# Base_Station_2_5.net
KiCad netlist of a schematic drawn in EAGLE
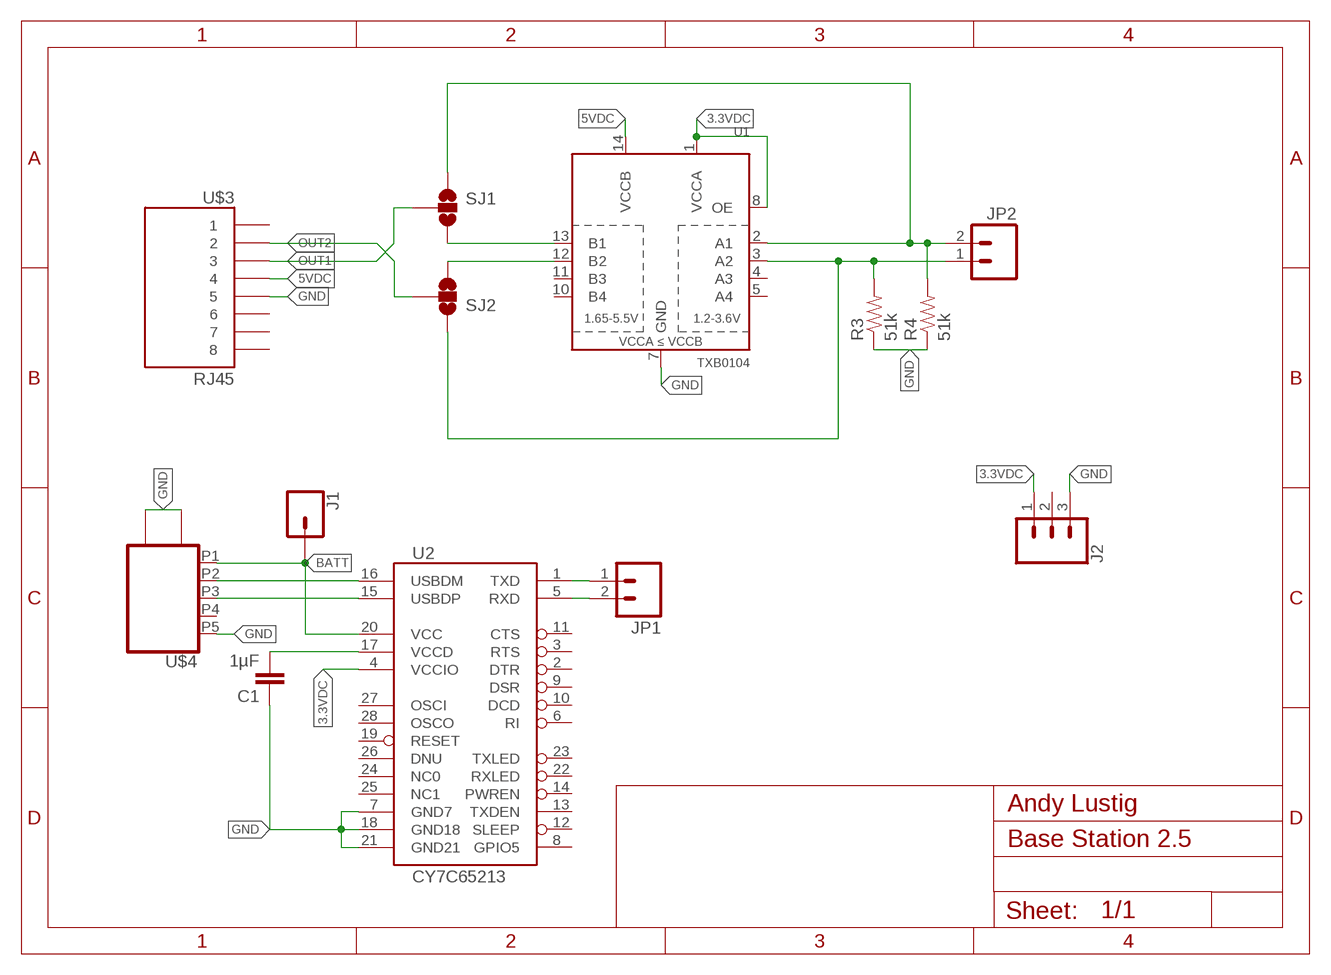
[diagram p0: schematic, sheet 1]

(export (version "E")
  (design (tool "Eeschema 10.0.6"))
  (components
    (comp (ref "C1")
      (value "1µF")
      (footprint "eagle-import:0603")
      (libsource (lib "eagle-import") (part "0.1UF-0603-25V-5%"))
    )
    (comp (ref "J1")
      (value "CONN_01PTH_NO_SILK_YES_STOP")
      (footprint "eagle-import:1X01_NO_SILK")
      (libsource (lib "eagle-import") (part "CONN_01PTH_NO_SILK_YES_STOP"))
    )
    (comp (ref "J2")
      (value "CONN_031X03_NO_SILK")
      (footprint "eagle-import:1X03_NO_SILK")
      (libsource (lib "eagle-import") (part "CONN_031X03_NO_SILK"))
    )
    (comp (ref "JP1")
      (value "M021X02_NO_SILK")
      (footprint "eagle-import:1X02_NO_SILK")
      (libsource (lib "eagle-import") (part "M021X02_NO_SILK"))
    )
    (comp (ref "JP2")
      (value "M021X02_NO_SILK")
      (footprint "eagle-import:1X02_NO_SILK")
      (libsource (lib "eagle-import") (part "M021X02_NO_SILK"))
    )
    (comp (ref "R3")
      (value "51k")
      (footprint "eagle-import:0805")
      (libsource (lib "eagle-import") (part "RESISTOR0805-RES"))
    )
    (comp (ref "R4")
      (value "51k")
      (footprint "eagle-import:0805")
      (libsource (lib "eagle-import") (part "RESISTOR0805-RES"))
    )
    (comp (ref "SJ1")
      (value "SOLDERJUMPER_2WAYPASTE2&3")
      (footprint "eagle-import:SJ_3_PASTE2&3")
      (libsource (lib "eagle-import") (part "SOLDERJUMPER_2WAYPASTE2&3"))
    )
    (comp (ref "SJ2")
      (value "SOLDERJUMPER_2WAYPASTE2&3")
      (footprint "eagle-import:SJ_3_PASTE2&3")
      (libsource (lib "eagle-import") (part "SOLDERJUMPER_2WAYPASTE2&3"))
    )
    (comp (ref "U$3")
      (value "RJ45")
      (footprint "eagle-import:RJ45-8")
      (libsource (lib "eagle-import") (part "RJ45"))
    )
    (comp (ref "U$4")
      (value "USB_MICRO_SOCKET_HORZ_REINFORCED")
      (footprint "eagle-import:USB_HORZ_REINFORCED_MICRO")
      (libsource (lib "eagle-import") (part "USB_MICRO_SOCKET_HORZ_REINFORCED"))
    )
    (comp (ref "U1")
      (value "TXB0104")
      (footprint "eagle-import:TSSOP14")
      (libsource (lib "eagle-import") (part "TXB0104PWR"))
    )
    (comp (ref "U2")
      (value "CY7C65213")
      (footprint "eagle-import:SSOP28DB")
      (libsource (lib "eagle-import") (part "CY7C65213"))
    )
  )
  (nets
    (net (code "1") (name "/NC1") (class "Default")
      (node (ref "U2") (pin "25") (pinfunction "NC1_25") (pintype "power_in"))
    )
    (net (code "2") (name "3.3VDC") (class "Default")
      (node (ref "J2") (pin "1") (pinfunction "1_1") (pintype "passive"))
      (node (ref "U1") (pin "1") (pinfunction "VCCA_1") (pintype "bidirectional"))
      (node (ref "U1") (pin "8") (pinfunction "OE_8") (pintype "bidirectional"))
      (node (ref "U2") (pin "4") (pinfunction "VCCIO_4") (pintype "power_in"))
    )
    (net (code "3") (name "5VDC") (class "Default")
      (node (ref "U$3") (pin "4") (pinfunction "4_4") (pintype "bidirectional"))
      (node (ref "U1") (pin "14") (pinfunction "VCCB_14") (pintype "bidirectional"))
    )
    (net (code "4") (name "BATT") (class "Default")
      (node (ref "J1") (pin "1") (pinfunction "1_1") (pintype "passive"))
      (node (ref "U$4") (pin "P1") (pinfunction "P1_P1") (pintype "bidirectional"))
      (node (ref "U2") (pin "20") (pinfunction "VCC_20") (pintype "power_in"))
    )
    (net (code "5") (name "GND") (class "Default")
      (node (ref "C1") (pin "1") (pinfunction "1_1") (pintype "passive"))
      (node (ref "J2") (pin "3") (pinfunction "3_3") (pintype "passive"))
      (node (ref "R3") (pin "1") (pinfunction "1_1") (pintype "passive"))
      (node (ref "R4") (pin "1") (pinfunction "1_1") (pintype "passive"))
      (node (ref "U$3") (pin "5") (pinfunction "5_5") (pintype "bidirectional"))
      (node (ref "U$4") (pin "G1") (pinfunction "P$1_G1") (pintype "bidirectional"))
      (node (ref "U$4") (pin "G2") (pinfunction "P$1_G2") (pintype "bidirectional"))
      (node (ref "U$4") (pin "P$1") (pinfunction "P$2_P$1") (pintype "bidirectional"))
      (node (ref "U$4") (pin "P$2") (pinfunction "P$2_P$2") (pintype "bidirectional"))
      (node (ref "U$4") (pin "P5") (pinfunction "P5_P5") (pintype "bidirectional"))
      (node (ref "U1") (pin "7") (pinfunction "GND_7") (pintype "bidirectional"))
      (node (ref "U2") (pin "18") (pinfunction "GND18_18") (pintype "power_in"))
      (node (ref "U2") (pin "21") (pinfunction "GND21_21") (pintype "power_in"))
      (node (ref "U2") (pin "7") (pinfunction "GND7_7") (pintype "power_in"))
    )
    (net (code "6") (name "Net-(U1-A1)") (class "Default")
      (node (ref "JP2") (pin "2") (pinfunction "2_2") (pintype "passive"))
      (node (ref "R4") (pin "2") (pinfunction "2_2") (pintype "passive"))
      (node (ref "SJ1") (pin "1") (pinfunction "1_1") (pintype "passive"))
      (node (ref "U1") (pin "2") (pinfunction "A1_2") (pintype "bidirectional"))
    )
    (net (code "7") (name "Net-(U1-A2)") (class "Default")
      (node (ref "JP2") (pin "1") (pinfunction "1_1") (pintype "passive"))
      (node (ref "R3") (pin "2") (pinfunction "2_2") (pintype "passive"))
      (node (ref "SJ2") (pin "1") (pinfunction "1_1") (pintype "passive"))
      (node (ref "U1") (pin "3") (pinfunction "A2_3") (pintype "bidirectional"))
    )
    (net (code "8") (name "Net-(U1-B1)") (class "Default")
      (node (ref "SJ1") (pin "3") (pinfunction "3_3") (pintype "passive"))
      (node (ref "U1") (pin "13") (pinfunction "B1_13") (pintype "bidirectional"))
    )
    (net (code "9") (name "Net-(U1-B2)") (class "Default")
      (node (ref "SJ2") (pin "3") (pinfunction "3_3") (pintype "passive"))
      (node (ref "U1") (pin "12") (pinfunction "B2_12") (pintype "bidirectional"))
    )
    (net (code "10") (name "Net-(U2-RXD)") (class "Default")
      (node (ref "JP1") (pin "2") (pinfunction "2_2") (pintype "passive"))
      (node (ref "U2") (pin "5") (pinfunction "RXD_5") (pintype "input"))
    )
    (net (code "11") (name "Net-(U2-TXD)") (class "Default")
      (node (ref "JP1") (pin "1") (pinfunction "1_1") (pintype "passive"))
      (node (ref "U2") (pin "1") (pinfunction "TXD_1") (pintype "output"))
    )
    (net (code "12") (name "Net-(U2-USBDM)") (class "Default")
      (node (ref "U$4") (pin "P2") (pinfunction "P2_P2") (pintype "bidirectional"))
      (node (ref "U2") (pin "16") (pinfunction "USBDM_16") (pintype "bidirectional"))
    )
    (net (code "13") (name "Net-(U2-USBDP)") (class "Default")
      (node (ref "U$4") (pin "P3") (pinfunction "P3_P3") (pintype "bidirectional"))
      (node (ref "U2") (pin "15") (pinfunction "USBDP_15") (pintype "bidirectional"))
    )
    (net (code "14") (name "Net-(U2-VCCD)") (class "Default")
      (node (ref "C1") (pin "2") (pinfunction "2_2") (pintype "passive"))
      (node (ref "U2") (pin "17") (pinfunction "VCCD_17") (pintype "output"))
    )
    (net (code "15") (name "OUT1") (class "Default")
      (node (ref "SJ1") (pin "2") (pinfunction "2_2") (pintype "passive"))
      (node (ref "U$3") (pin "3") (pinfunction "3_3") (pintype "bidirectional"))
    )
    (net (code "16") (name "OUT2") (class "Default")
      (node (ref "SJ2") (pin "2") (pinfunction "2_2") (pintype "passive"))
      (node (ref "U$3") (pin "2") (pinfunction "2_2") (pintype "bidirectional"))
    )
    (net (code "17") (name "unconnected-(J2-Pad2)") (class "Default")
      (node (ref "J2") (pin "2") (pinfunction "2_2") (pintype "passive"))
    )
    (net (code "18") (name "unconnected-(U$3-Pad1)") (class "Default")
      (node (ref "U$3") (pin "1") (pinfunction "1_1") (pintype "bidirectional"))
    )
    (net (code "19") (name "unconnected-(U$3-Pad6)") (class "Default")
      (node (ref "U$3") (pin "6") (pinfunction "6_6") (pintype "bidirectional"))
    )
    (net (code "20") (name "unconnected-(U$3-Pad7)") (class "Default")
      (node (ref "U$3") (pin "7") (pinfunction "7_7") (pintype "bidirectional"))
    )
    (net (code "21") (name "unconnected-(U$3-Pad8)") (class "Default")
      (node (ref "U$3") (pin "8") (pinfunction "8_8") (pintype "bidirectional"))
    )
    (net (code "22") (name "unconnected-(U$4-PadP4)") (class "Default")
      (node (ref "U$4") (pin "P4") (pinfunction "P4_P4") (pintype "bidirectional"))
    )
    (net (code "23") (name "unconnected-(U1-A3-Pad4)") (class "Default")
      (node (ref "U1") (pin "4") (pinfunction "A3_4") (pintype "bidirectional"))
    )
    (net (code "24") (name "unconnected-(U1-A4-Pad5)") (class "Default")
      (node (ref "U1") (pin "5") (pinfunction "A4_5") (pintype "bidirectional"))
    )
    (net (code "25") (name "unconnected-(U1-B3-Pad11)") (class "Default")
      (node (ref "U1") (pin "11") (pinfunction "B3_11") (pintype "bidirectional"))
    )
    (net (code "26") (name "unconnected-(U1-B4-Pad10)") (class "Default")
      (node (ref "U1") (pin "10") (pinfunction "B4_10") (pintype "bidirectional"))
    )
    (net (code "27") (name "unconnected-(U2-CTS-Pad11)") (class "Default")
      (node (ref "U2") (pin "11") (pinfunction "CTS_11") (pintype "input"))
    )
    (net (code "28") (name "unconnected-(U2-DCD-Pad10)") (class "Default")
      (node (ref "U2") (pin "10") (pinfunction "DCD_10") (pintype "input"))
    )
    (net (code "29") (name "unconnected-(U2-DNU-Pad26)") (class "Default")
      (node (ref "U2") (pin "26") (pinfunction "DNU_26") (pintype "input"))
    )
    (net (code "30") (name "unconnected-(U2-DSR-Pad9)") (class "Default")
      (node (ref "U2") (pin "9") (pinfunction "DSR_9") (pintype "input"))
    )
    (net (code "31") (name "unconnected-(U2-DTR-Pad2)") (class "Default")
      (node (ref "U2") (pin "2") (pinfunction "DTR_2") (pintype "output"))
    )
    (net (code "32") (name "unconnected-(U2-GPIO5-Pad8)") (class "Default")
      (node (ref "U2") (pin "8") (pinfunction "GPIO5_8") (pintype "input"))
    )
    (net (code "33") (name "unconnected-(U2-NC0-Pad24)") (class "Default")
      (node (ref "U2") (pin "24") (pinfunction "NC0_24") (pintype "input"))
    )
    (net (code "34") (name "unconnected-(U2-OSCI-Pad27)") (class "Default")
      (node (ref "U2") (pin "27") (pinfunction "OSCI_27") (pintype "input"))
    )
    (net (code "35") (name "unconnected-(U2-OSCO-Pad28)") (class "Default")
      (node (ref "U2") (pin "28") (pinfunction "OSCO_28") (pintype "output"))
    )
    (net (code "36") (name "unconnected-(U2-PWREN-Pad14)") (class "Default")
      (node (ref "U2") (pin "14") (pinfunction "PWREN_14") (pintype "input"))
    )
    (net (code "37") (name "unconnected-(U2-RESET-Pad19)") (class "Default")
      (node (ref "U2") (pin "19") (pinfunction "RESET_19") (pintype "input"))
    )
    (net (code "38") (name "unconnected-(U2-RI-Pad6)") (class "Default")
      (node (ref "U2") (pin "6") (pinfunction "RI_6") (pintype "input"))
    )
    (net (code "39") (name "unconnected-(U2-RTS-Pad3)") (class "Default")
      (node (ref "U2") (pin "3") (pinfunction "RTS_3") (pintype "output"))
    )
    (net (code "40") (name "unconnected-(U2-RXLED-Pad22)") (class "Default")
      (node (ref "U2") (pin "22") (pinfunction "RXLED_22") (pintype "input"))
    )
    (net (code "41") (name "unconnected-(U2-SLEEP-Pad12)") (class "Default")
      (node (ref "U2") (pin "12") (pinfunction "SLEEP_12") (pintype "input"))
    )
    (net (code "42") (name "unconnected-(U2-TXDEN-Pad13)") (class "Default")
      (node (ref "U2") (pin "13") (pinfunction "TXDEN_13") (pintype "input"))
    )
    (net (code "43") (name "unconnected-(U2-TXLED-Pad23)") (class "Default")
      (node (ref "U2") (pin "23") (pinfunction "TXLED_23") (pintype "input"))
    )
  )
)
